# 11.net
KiCad netlist of a schematic drawn in Altium Designer
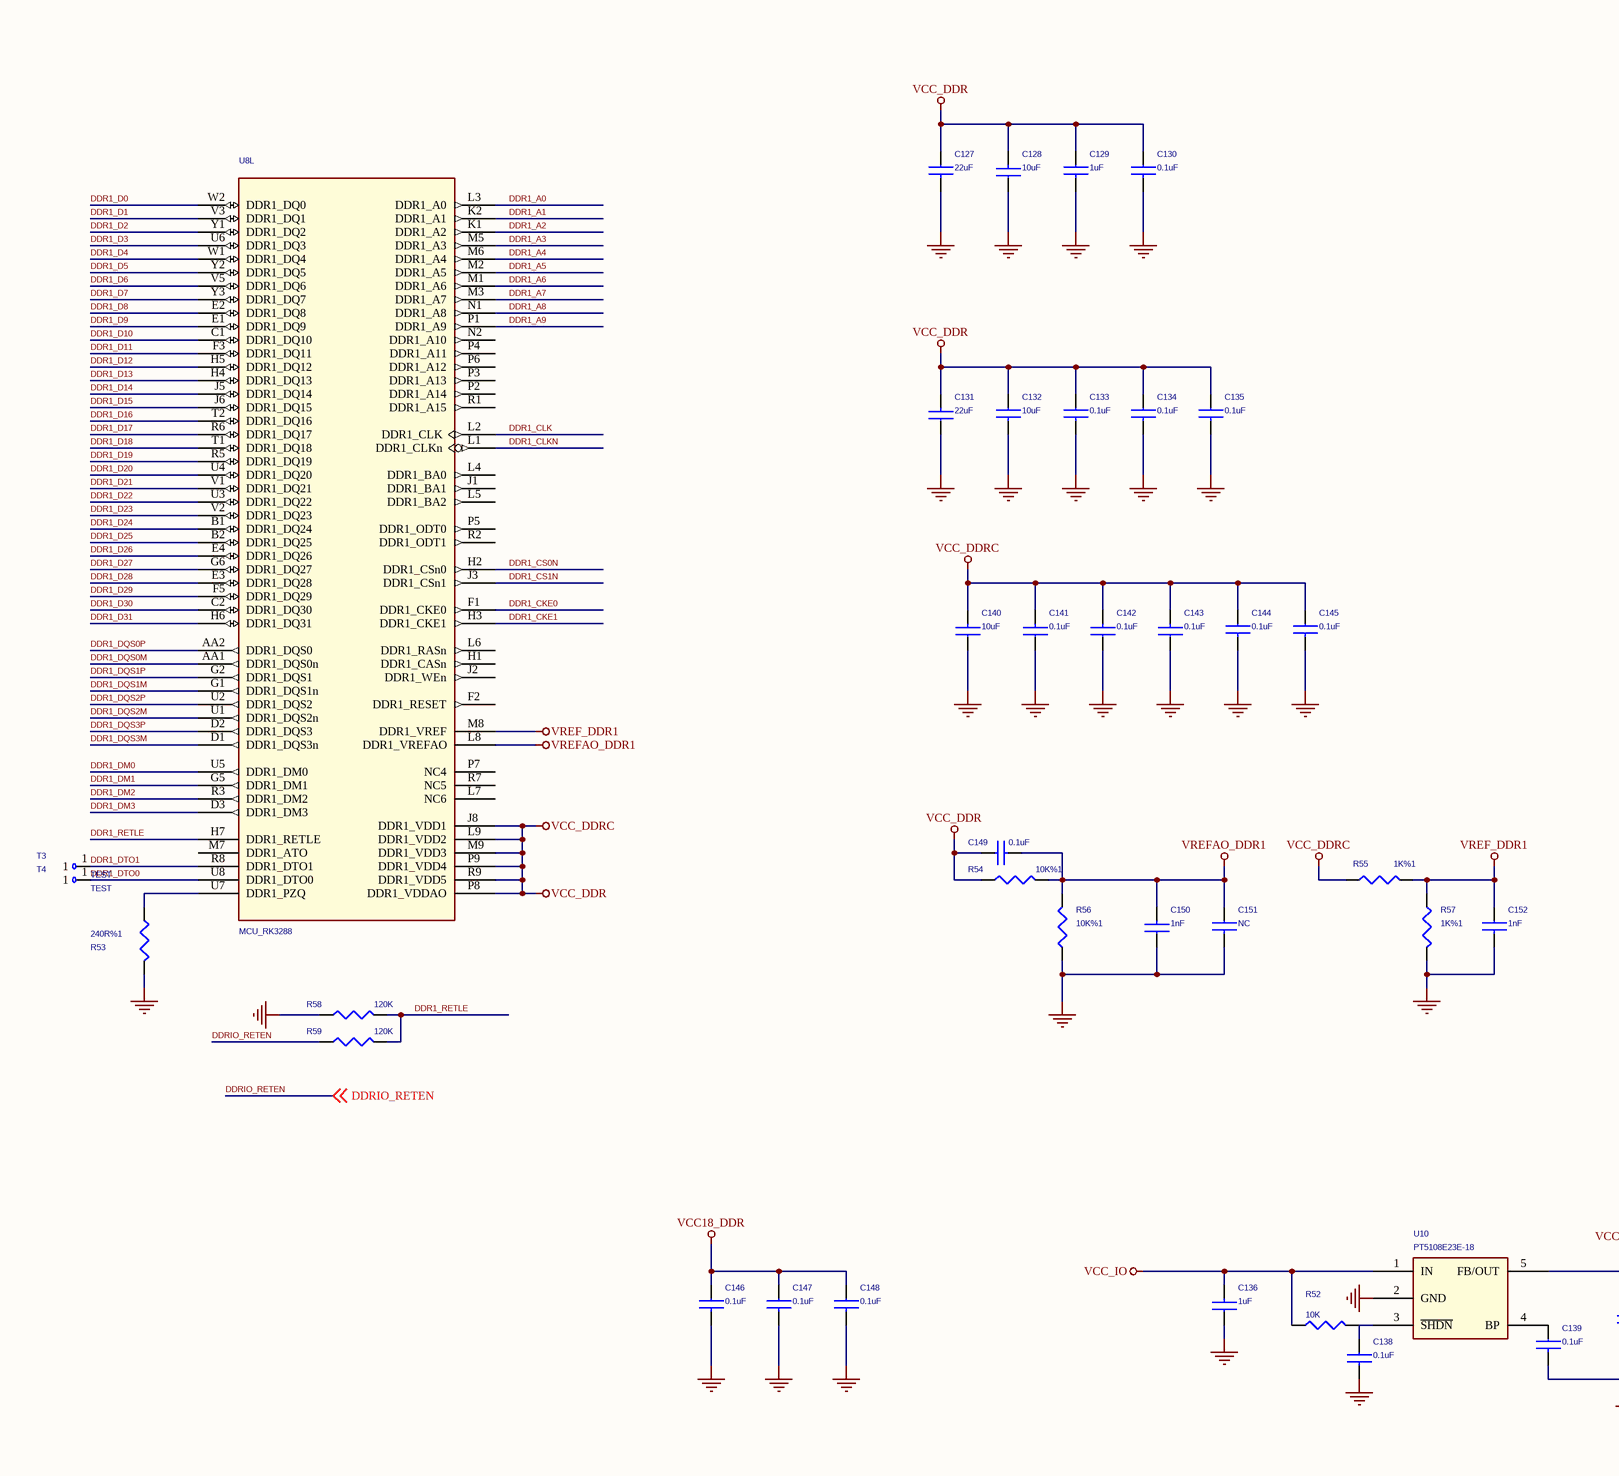
[diagram p0: 11.SchDoc, left]
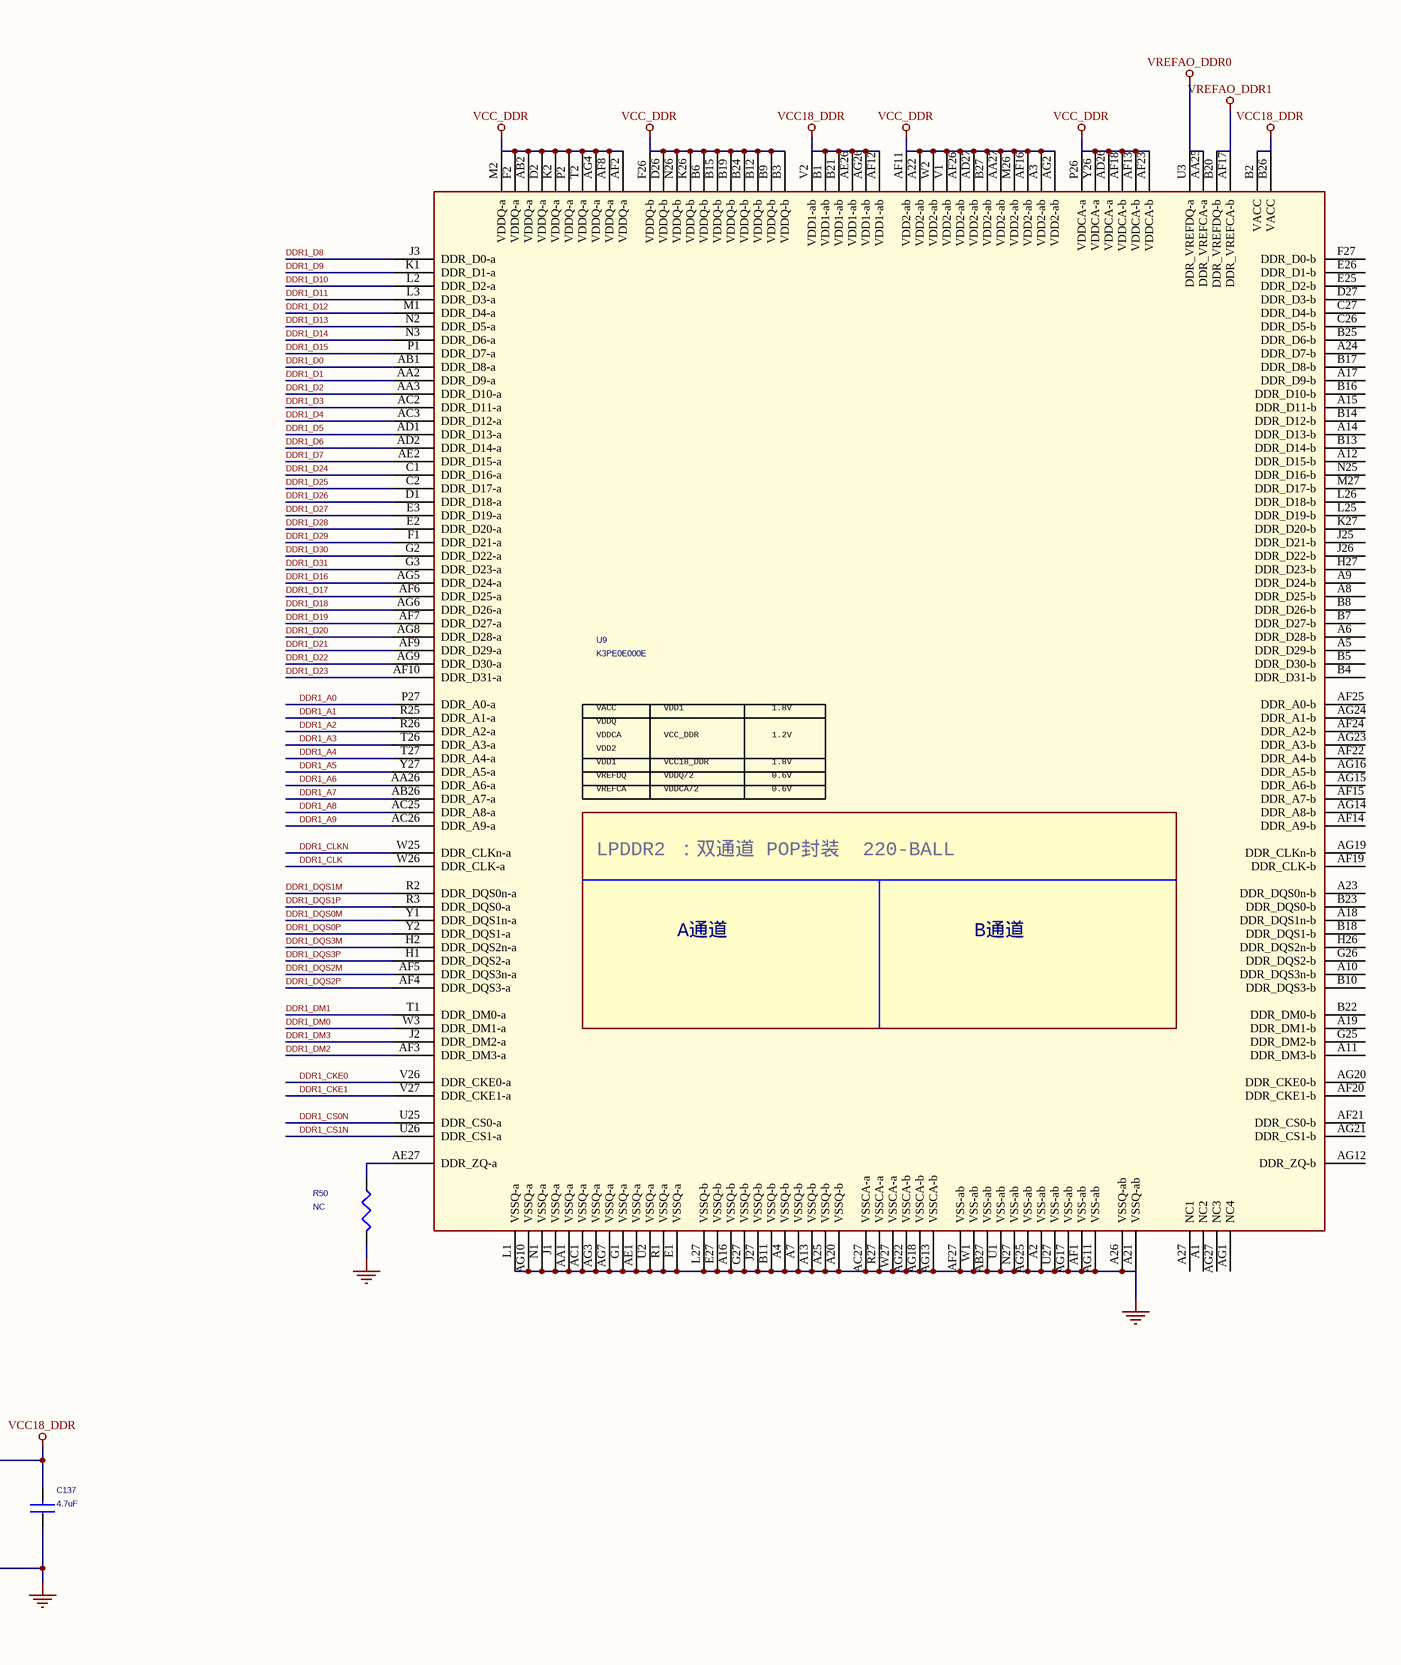
[diagram p1: 11.SchDoc, right]

(export (version "E")
  (design (tool "Eeschema 10.0.6"))
  (components
    (comp (ref "C127") (value "22uF") (footprint "C0805") (libsource (lib "*") (part "CAP NP_0_Dup1")))
    (comp (ref "C128") (value "10uF") (footprint "C0603") (libsource (lib "*") (part "CAP NP_4")))
    (comp (ref "C129") (value "1uF") (footprint "c0402") (libsource (lib "*") (part "CAP NP_0_Dup1")))
    (comp (ref "C130") (value "0.1uF") (footprint "c0402") (libsource (lib "*") (part "CAP NP_0_Dup1")))
    (comp (ref "C131") (value "22uF") (footprint "C0805") (libsource (lib "*") (part "CAP NP_4")))
    (comp (ref "C132") (value "10uF") (footprint "C0603") (libsource (lib "*") (part "CAP NP_0_Dup1")))
    (comp (ref "C133") (value "0.1uF") (footprint "c0402") (libsource (lib "*") (part "CAP NP_0_Dup1")))
    (comp (ref "C134") (value "0.1uF") (footprint "c0402") (libsource (lib "*") (part "CAP NP_0_Dup1")))
    (comp (ref "C135") (value "0.1uF") (footprint "C0201") (libsource (lib "*") (part "CAP NP_0_Dup1")))
    (comp (ref "C136")
      (value "1uF")
      (footprint "c0402")
      (description "CAP,MLCC,10uF,+/-10%,X5R,6.3V,SMD0805")
      (libsource (lib "*") (part "CAP NP_4"))
    )
    (comp (ref "C137")
      (value "4.7uF")
      (footprint "C0603")
      (description "CAP,MLCC,10uF,+/-10%,X5R,6.3V,SMD0805")
      (libsource (lib "*") (part "CAP NP_4"))
    )
    (comp (ref "C138")
      (value "0.1uF")
      (footprint "c0402")
      (description "CAP,MLCC,100nF,+/-10%,X7R,6.3V,SMD0402")
      (libsource (lib "*") (part "CAP NP_4"))
    )
    (comp (ref "C139")
      (value "0.1uF")
      (footprint "c0402")
      (description "CAP,MLCC,100nF,+/-10%,X7R,6.3V,SMD0402")
      (libsource (lib "*") (part "CAP NP_4"))
    )
    (comp (ref "C140") (value "10uF") (footprint "C0603") (libsource (lib "*") (part "CAP NP_4")))
    (comp (ref "C141") (value "0.1uF") (footprint "c0402") (libsource (lib "*") (part "CAP NP_4")))
    (comp (ref "C142") (value "0.1uF") (footprint "c0402") (libsource (lib "*") (part "CAP NP_4")))
    (comp (ref "C143") (value "0.1uF") (footprint "c0402") (libsource (lib "*") (part "CAP NP_4")))
    (comp (ref "C144") (value "0.1uF") (footprint "c0402") (libsource (lib "*") (part "CAP NP_0_Dup1")))
    (comp (ref "C145") (value "0.1uF") (footprint "c0402") (libsource (lib "*") (part "CAP NP_0_Dup1")))
    (comp (ref "C146") (value "0.1uF") (footprint "c0402") (libsource (lib "*") (part "CAP NP_0_Dup1")))
    (comp (ref "C147") (value "0.1uF") (footprint "c0402") (libsource (lib "*") (part "CAP NP_0_Dup1")))
    (comp (ref "C148") (value "0.1uF") (footprint "C0201") (libsource (lib "*") (part "CAP NP_0_Dup1")))
    (comp (ref "C149") (value "0.1uF") (footprint "c0402") (libsource (lib "*") (part "CAP NP_0_Dup1")))
    (comp (ref "C150") (value "1nF") (footprint "C0201") (libsource (lib "*") (part "CAP NP_0_Dup1")))
    (comp (ref "C151") (value "NC") (footprint "c0402") (libsource (lib "*") (part "CAP NP_0_Dup1")))
    (comp (ref "C152") (value "1nF") (footprint "c0402") (libsource (lib "*") (part "CAP NP_0_Dup1")))
    (comp (ref "R50")
      (value "NC")
      (footprint "r0402")
      (description "贴片电阻")
      (libsource (lib "*") (part "RESISTOR_0_Dup1"))
    )
    (comp (ref "R52")
      (value "10K")
      (footprint "r0402")
      (description "贴片电阻")
      (libsource (lib "*") (part "RESISTOR_0_Dup1"))
    )
    (comp (ref "R53")
      (value "240R%1")
      (footprint "r0402")
      (description "贴片电阻")
      (libsource (lib "*") (part "RESISTOR_0_Dup1"))
    )
    (comp (ref "R54")
      (value "10K%1")
      (footprint "r0402")
      (description "贴片电阻")
      (libsource (lib "*") (part "RESISTOR_0_Dup1"))
    )
    (comp (ref "R55")
      (value "1K%1")
      (footprint "r0402")
      (description "贴片电阻")
      (libsource (lib "*") (part "RESISTOR_0_Dup1"))
    )
    (comp (ref "R56")
      (value "10K%1")
      (footprint "r0402")
      (description "贴片电阻")
      (libsource (lib "*") (part "RESISTOR_0_Dup1"))
    )
    (comp (ref "R57")
      (value "1K%1")
      (footprint "r0402")
      (description "贴片电阻")
      (libsource (lib "*") (part "RESISTOR_0_Dup1"))
    )
    (comp (ref "R58")
      (value "120K")
      (footprint "r0402")
      (description "贴片电阻")
      (libsource (lib "*") (part "RESISTOR_0_Dup1"))
    )
    (comp (ref "R59")
      (value "120K")
      (footprint "r0402")
      (description "贴片电阻")
      (libsource (lib "*") (part "RESISTOR_0_Dup1"))
    )
    (comp (ref "T3") (value "TEST") (footprint "TEST") (libsource (lib "*") (part "TEST_0")))
    (comp (ref "T4") (value "TEST") (footprint "TEST") (libsource (lib "*") (part "TEST_0")))
    (comp (ref "U8")
      (value "MCU_RK3288")
      (footprint "BGA453-19X19")
      (libsource (lib "*") (part "MCU_RK3288_3"))
    )
    (comp (ref "U9")
      (value "K3PE0E000E")
      (footprint "FBGA220-14X14")
      (libsource (lib "*") (part "K3PE0E000E_1"))
    )
    (comp (ref "U10")
      (value "PT5108E23E-18")
      (footprint "SOT25")
      (description "LDO,PT5108E23E-33,VINmax=5.5V,Vout=3.3V,+/-2%,500mA,SOT-23-5")
      (libsource (lib "*") (part "DS8008_4"))
    )
  )
  (nets
    (net (code "1") (name "/DDR1_A0") (class "Default")
      (node (ref "U8") (pin "L3") (pinfunction "DDR1_A0_L3") (pintype "output"))
      (node (ref "U9") (pin "P27") (pinfunction "DDR_A0-a_P27") (pintype "passive"))
    )
    (net (code "2") (name "/DDR1_A1") (class "Default")
      (node (ref "U8") (pin "K2") (pinfunction "DDR1_A1_K2") (pintype "output"))
      (node (ref "U9") (pin "R25") (pinfunction "DDR_A1-a_R25") (pintype "passive"))
    )
    (net (code "3") (name "/DDR1_A2") (class "Default")
      (node (ref "U8") (pin "K1") (pinfunction "DDR1_A2_K1") (pintype "output"))
      (node (ref "U9") (pin "R26") (pinfunction "DDR_A2-a_R26") (pintype "passive"))
    )
    (net (code "4") (name "/DDR1_A3") (class "Default")
      (node (ref "U8") (pin "M5") (pinfunction "DDR1_A3_M5") (pintype "output"))
      (node (ref "U9") (pin "T26") (pinfunction "DDR_A3-a_T26") (pintype "passive"))
    )
    (net (code "5") (name "/DDR1_A4") (class "Default")
      (node (ref "U8") (pin "M6") (pinfunction "DDR1_A4_M6") (pintype "output"))
      (node (ref "U9") (pin "T27") (pinfunction "DDR_A4-a_T27") (pintype "passive"))
    )
    (net (code "6") (name "/DDR1_A5") (class "Default")
      (node (ref "U8") (pin "M2") (pinfunction "DDR1_A5_M2") (pintype "output"))
      (node (ref "U9") (pin "Y27") (pinfunction "DDR_A5-a_Y27") (pintype "passive"))
    )
    (net (code "7") (name "/DDR1_A6") (class "Default")
      (node (ref "U8") (pin "M1") (pinfunction "DDR1_A6_M1") (pintype "output"))
      (node (ref "U9") (pin "AA26") (pinfunction "DDR_A6-a_AA26") (pintype "passive"))
    )
    (net (code "8") (name "/DDR1_A7") (class "Default")
      (node (ref "U8") (pin "M3") (pinfunction "DDR1_A7_M3") (pintype "output"))
      (node (ref "U9") (pin "AB26") (pinfunction "DDR_A7-a_AB26") (pintype "passive"))
    )
    (net (code "9") (name "/DDR1_A8") (class "Default")
      (node (ref "U8") (pin "N1") (pinfunction "DDR1_A8_N1") (pintype "output"))
      (node (ref "U9") (pin "AC25") (pinfunction "DDR_A8-a_AC25") (pintype "passive"))
    )
    (net (code "10") (name "/DDR1_A9") (class "Default")
      (node (ref "U8") (pin "P1") (pinfunction "DDR1_A9_P1") (pintype "output"))
      (node (ref "U9") (pin "AC26") (pinfunction "DDR_A9-a_AC26") (pintype "passive"))
    )
    (net (code "11") (name "/DDR1_CKE0") (class "Default")
      (node (ref "U8") (pin "F1") (pinfunction "DDR1_CKE0_F1") (pintype "output"))
      (node (ref "U9") (pin "V26") (pinfunction "DDR_CKE0-a_V26") (pintype "passive"))
    )
    (net (code "12") (name "/DDR1_CKE1") (class "Default")
      (node (ref "U8") (pin "H3") (pinfunction "DDR1_CKE1_H3") (pintype "output"))
      (node (ref "U9") (pin "V27") (pinfunction "DDR_CKE1-a_V27") (pintype "passive"))
    )
    (net (code "13") (name "/DDR1_CLK") (class "Default")
      (node (ref "U8") (pin "L2") (pinfunction "DDR1_CLK_L2") (pintype "output"))
      (node (ref "U9") (pin "W26") (pinfunction "DDR_CLK-a_W26") (pintype "passive"))
    )
    (net (code "14") (name "/DDR1_CLKN") (class "Default")
      (node (ref "U8") (pin "L1") (pinfunction "DDR1_CLKn_L1") (pintype "output"))
      (node (ref "U9") (pin "W25") (pinfunction "DDR_CLKn-a_W25") (pintype "passive"))
    )
    (net (code "15") (name "/DDR1_CS0N") (class "Default")
      (node (ref "U8") (pin "H2") (pinfunction "DDR1_CSn0_H2") (pintype "output"))
      (node (ref "U9") (pin "U25") (pinfunction "DDR_CS0-a_U25") (pintype "passive"))
    )
    (net (code "16") (name "/DDR1_CS1N") (class "Default")
      (node (ref "U8") (pin "J3") (pinfunction "DDR1_CSn1_J3") (pintype "output"))
      (node (ref "U9") (pin "U26") (pinfunction "DDR_CS1-a_U26") (pintype "passive"))
    )
    (net (code "17") (name "/DDR1_D0") (class "Default")
      (node (ref "U8") (pin "W2") (pinfunction "DDR1_DQ0_W2") (pintype "bidirectional"))
      (node (ref "U9") (pin "AB1") (pinfunction "DDR_D8-a_AB1") (pintype "passive"))
    )
    (net (code "18") (name "/DDR1_D1") (class "Default")
      (node (ref "U8") (pin "V3") (pinfunction "DDR1_DQ1_V3") (pintype "bidirectional"))
      (node (ref "U9") (pin "AA2") (pinfunction "DDR_D9-a_AA2") (pintype "passive"))
    )
    (net (code "19") (name "/DDR1_D2") (class "Default")
      (node (ref "U8") (pin "Y1") (pinfunction "DDR1_DQ2_Y1") (pintype "bidirectional"))
      (node (ref "U9") (pin "AA3") (pinfunction "DDR_D10-a_AA3") (pintype "passive"))
    )
    (net (code "20") (name "/DDR1_D3") (class "Default")
      (node (ref "U8") (pin "U6") (pinfunction "DDR1_DQ3_U6") (pintype "bidirectional"))
      (node (ref "U9") (pin "AC2") (pinfunction "DDR_D11-a_AC2") (pintype "passive"))
    )
    (net (code "21") (name "/DDR1_D4") (class "Default")
      (node (ref "U8") (pin "W1") (pinfunction "DDR1_DQ4_W1") (pintype "bidirectional"))
      (node (ref "U9") (pin "AC3") (pinfunction "DDR_D12-a_AC3") (pintype "passive"))
    )
    (net (code "22") (name "/DDR1_D5") (class "Default")
      (node (ref "U8") (pin "Y2") (pinfunction "DDR1_DQ5_Y2") (pintype "bidirectional"))
      (node (ref "U9") (pin "AD1") (pinfunction "DDR_D13-a_AD1") (pintype "passive"))
    )
    (net (code "23") (name "/DDR1_D6") (class "Default")
      (node (ref "U8") (pin "V5") (pinfunction "DDR1_DQ6_V5") (pintype "bidirectional"))
      (node (ref "U9") (pin "AD2") (pinfunction "DDR_D14-a_AD2") (pintype "passive"))
    )
    (net (code "24") (name "/DDR1_D7") (class "Default")
      (node (ref "U8") (pin "Y3") (pinfunction "DDR1_DQ7_Y3") (pintype "bidirectional"))
      (node (ref "U9") (pin "AE2") (pinfunction "DDR_D15-a_AE2") (pintype "passive"))
    )
    (net (code "25") (name "/DDR1_D8") (class "Default")
      (node (ref "U8") (pin "E2") (pinfunction "DDR1_DQ8_E2") (pintype "bidirectional"))
      (node (ref "U9") (pin "J3") (pinfunction "DDR_D0-a_J3") (pintype "passive"))
    )
    (net (code "26") (name "/DDR1_D9") (class "Default")
      (node (ref "U8") (pin "E1") (pinfunction "DDR1_DQ9_E1") (pintype "bidirectional"))
      (node (ref "U9") (pin "K1") (pinfunction "DDR_D1-a_K1") (pintype "passive"))
    )
    (net (code "27") (name "/DDR1_D10") (class "Default")
      (node (ref "U8") (pin "C1") (pinfunction "DDR1_DQ10_C1") (pintype "bidirectional"))
      (node (ref "U9") (pin "L2") (pinfunction "DDR_D2-a_L2") (pintype "passive"))
    )
    (net (code "28") (name "/DDR1_D11") (class "Default")
      (node (ref "U8") (pin "F3") (pinfunction "DDR1_DQ11_F3") (pintype "bidirectional"))
      (node (ref "U9") (pin "L3") (pinfunction "DDR_D3-a_L3") (pintype "passive"))
    )
    (net (code "29") (name "/DDR1_D12") (class "Default")
      (node (ref "U8") (pin "H5") (pinfunction "DDR1_DQ12_H5") (pintype "bidirectional"))
      (node (ref "U9") (pin "M1") (pinfunction "DDR_D4-a_M1") (pintype "passive"))
    )
    (net (code "30") (name "/DDR1_D13") (class "Default")
      (node (ref "U8") (pin "H4") (pinfunction "DDR1_DQ13_H4") (pintype "bidirectional"))
      (node (ref "U9") (pin "N2") (pinfunction "DDR_D5-a_N2") (pintype "passive"))
    )
    (net (code "31") (name "/DDR1_D14") (class "Default")
      (node (ref "U8") (pin "J5") (pinfunction "DDR1_DQ14_J5") (pintype "bidirectional"))
      (node (ref "U9") (pin "N3") (pinfunction "DDR_D6-a_N3") (pintype "passive"))
    )
    (net (code "32") (name "/DDR1_D15") (class "Default")
      (node (ref "U8") (pin "J6") (pinfunction "DDR1_DQ15_J6") (pintype "bidirectional"))
      (node (ref "U9") (pin "P1") (pinfunction "DDR_D7-a_P1") (pintype "passive"))
    )
    (net (code "33") (name "/DDR1_D16") (class "Default")
      (node (ref "U8") (pin "T2") (pinfunction "DDR1_DQ16_T2") (pintype "bidirectional"))
      (node (ref "U9") (pin "AG5") (pinfunction "DDR_D24-a_AG5") (pintype "passive"))
    )
    (net (code "34") (name "/DDR1_D17") (class "Default")
      (node (ref "U8") (pin "R6") (pinfunction "DDR1_DQ17_R6") (pintype "bidirectional"))
      (node (ref "U9") (pin "AF6") (pinfunction "DDR_D25-a_AF6") (pintype "passive"))
    )
    (net (code "35") (name "/DDR1_D18") (class "Default")
      (node (ref "U8") (pin "T1") (pinfunction "DDR1_DQ18_T1") (pintype "bidirectional"))
      (node (ref "U9") (pin "AG6") (pinfunction "DDR_D26-a_AG6") (pintype "passive"))
    )
    (net (code "36") (name "/DDR1_D19") (class "Default")
      (node (ref "U8") (pin "R5") (pinfunction "DDR1_DQ19_R5") (pintype "bidirectional"))
      (node (ref "U9") (pin "AF7") (pinfunction "DDR_D27-a_AF7") (pintype "passive"))
    )
    (net (code "37") (name "/DDR1_D20") (class "Default")
      (node (ref "U8") (pin "U4") (pinfunction "DDR1_DQ20_U4") (pintype "bidirectional"))
      (node (ref "U9") (pin "AG8") (pinfunction "DDR_D28-a_AG8") (pintype "passive"))
    )
    (net (code "38") (name "/DDR1_D21") (class "Default")
      (node (ref "U8") (pin "V1") (pinfunction "DDR1_DQ21_V1") (pintype "bidirectional"))
      (node (ref "U9") (pin "AF9") (pinfunction "DDR_D29-a_AF9") (pintype "passive"))
    )
    (net (code "39") (name "/DDR1_D22") (class "Default")
      (node (ref "U8") (pin "U3") (pinfunction "DDR1_DQ22_U3") (pintype "bidirectional"))
      (node (ref "U9") (pin "AG9") (pinfunction "DDR_D30-a_AG9") (pintype "passive"))
    )
    (net (code "40") (name "/DDR1_D23") (class "Default")
      (node (ref "U8") (pin "V2") (pinfunction "DDR1_DQ23_V2") (pintype "bidirectional"))
      (node (ref "U9") (pin "AF10") (pinfunction "DDR_D31-a_AF10") (pintype "passive"))
    )
    (net (code "41") (name "/DDR1_D24") (class "Default")
      (node (ref "U8") (pin "B1") (pinfunction "DDR1_DQ24_B1") (pintype "bidirectional"))
      (node (ref "U9") (pin "C1") (pinfunction "DDR_D16-a_C1") (pintype "passive"))
    )
    (net (code "42") (name "/DDR1_D25") (class "Default")
      (node (ref "U8") (pin "B2") (pinfunction "DDR1_DQ25_B2") (pintype "bidirectional"))
      (node (ref "U9") (pin "C2") (pinfunction "DDR_D17-a_C2") (pintype "passive"))
    )
    (net (code "43") (name "/DDR1_D26") (class "Default")
      (node (ref "U8") (pin "E4") (pinfunction "DDR1_DQ26_E4") (pintype "bidirectional"))
      (node (ref "U9") (pin "D1") (pinfunction "DDR_D18-a_D1") (pintype "passive"))
    )
    (net (code "44") (name "/DDR1_D27") (class "Default")
      (node (ref "U8") (pin "G6") (pinfunction "DDR1_DQ27_G6") (pintype "bidirectional"))
      (node (ref "U9") (pin "E3") (pinfunction "DDR_D19-a_E3") (pintype "passive"))
    )
    (net (code "45") (name "/DDR1_D28") (class "Default")
      (node (ref "U8") (pin "E3") (pinfunction "DDR1_DQ28_E3") (pintype "bidirectional"))
      (node (ref "U9") (pin "E2") (pinfunction "DDR_D20-a_E2") (pintype "passive"))
    )
    (net (code "46") (name "/DDR1_D29") (class "Default")
      (node (ref "U8") (pin "F5") (pinfunction "DDR1_DQ29_F5") (pintype "bidirectional"))
      (node (ref "U9") (pin "F1") (pinfunction "DDR_D21-a_F1") (pintype "passive"))
    )
    (net (code "47") (name "/DDR1_D30") (class "Default")
      (node (ref "U8") (pin "C2") (pinfunction "DDR1_DQ30_C2") (pintype "bidirectional"))
      (node (ref "U9") (pin "G2") (pinfunction "DDR_D22-a_G2") (pintype "passive"))
    )
    (net (code "48") (name "/DDR1_D31") (class "Default")
      (node (ref "U8") (pin "H6") (pinfunction "DDR1_DQ31_H6") (pintype "bidirectional"))
      (node (ref "U9") (pin "G3") (pinfunction "DDR_D23-a_G3") (pintype "passive"))
    )
    (net (code "49") (name "/DDR1_DM0") (class "Default")
      (node (ref "U8") (pin "U5") (pinfunction "DDR1_DM0_U5") (pintype "output"))
      (node (ref "U9") (pin "W3") (pinfunction "DDR_DM1-a_W3") (pintype "passive"))
    )
    (net (code "50") (name "/DDR1_DM1") (class "Default")
      (node (ref "U8") (pin "G5") (pinfunction "DDR1_DM1_G5") (pintype "output"))
      (node (ref "U9") (pin "T1") (pinfunction "DDR_DM0-a_T1") (pintype "passive"))
    )
    (net (code "51") (name "/DDR1_DM2") (class "Default")
      (node (ref "U8") (pin "R3") (pinfunction "DDR1_DM2_R3") (pintype "output"))
      (node (ref "U9") (pin "AF3") (pinfunction "DDR_DM3-a_AF3") (pintype "passive"))
    )
    (net (code "52") (name "/DDR1_DM3") (class "Default")
      (node (ref "U8") (pin "D3") (pinfunction "DDR1_DM3_D3") (pintype "output"))
      (node (ref "U9") (pin "J2") (pinfunction "DDR_DM2-a_J2") (pintype "passive"))
    )
    (net (code "53") (name "/DDR1_DQS0M") (class "Default")
      (node (ref "U8") (pin "AA1") (pinfunction "DDR1_DQS0n_AA1") (pintype "output"))
      (node (ref "U9") (pin "Y1") (pinfunction "DDR_DQS1n-a_Y1") (pintype "passive"))
    )
    (net (code "54") (name "/DDR1_DQS0P") (class "Default")
      (node (ref "U8") (pin "AA2") (pinfunction "DDR1_DQS0_AA2") (pintype "output"))
      (node (ref "U9") (pin "Y2") (pinfunction "DDR_DQS1-a_Y2") (pintype "passive"))
    )
    (net (code "55") (name "/DDR1_DQS1M") (class "Default")
      (node (ref "U8") (pin "G1") (pinfunction "DDR1_DQS1n_G1") (pintype "output"))
      (node (ref "U9") (pin "R2") (pinfunction "DDR_DQS0n-a_R2") (pintype "passive"))
    )
    (net (code "56") (name "/DDR1_DQS1P") (class "Default")
      (node (ref "U8") (pin "G2") (pinfunction "DDR1_DQS1_G2") (pintype "output"))
      (node (ref "U9") (pin "R3") (pinfunction "DDR_DQS0-a_R3") (pintype "passive"))
    )
    (net (code "57") (name "/DDR1_DQS2M") (class "Default")
      (node (ref "U8") (pin "U1") (pinfunction "DDR1_DQS2n_U1") (pintype "output"))
      (node (ref "U9") (pin "AF5") (pinfunction "DDR_DQS3n-a_AF5") (pintype "passive"))
    )
    (net (code "58") (name "/DDR1_DQS2P") (class "Default")
      (node (ref "U8") (pin "U2") (pinfunction "DDR1_DQS2_U2") (pintype "output"))
      (node (ref "U9") (pin "AF4") (pinfunction "DDR_DQS3-a_AF4") (pintype "passive"))
    )
    (net (code "59") (name "/DDR1_DQS3M") (class "Default")
      (node (ref "U8") (pin "D1") (pinfunction "DDR1_DQS3n_D1") (pintype "output"))
      (node (ref "U9") (pin "H2") (pinfunction "DDR_DQS2n-a_H2") (pintype "passive"))
    )
    (net (code "60") (name "/DDR1_DQS3P") (class "Default")
      (node (ref "U8") (pin "D2") (pinfunction "DDR1_DQS3_D2") (pintype "output"))
      (node (ref "U9") (pin "H1") (pinfunction "DDR_DQS2-a_H1") (pintype "passive"))
    )
    (net (code "61") (name "/DDR1_DTO0") (class "Default")
      (node (ref "T4") (pin "1") (pinfunction "1_1") (pintype "passive"))
      (node (ref "U8") (pin "U8") (pinfunction "DDR1_DTO0_U8") (pintype "passive"))
    )
    (net (code "62") (name "/DDR1_DTO1") (class "Default")
      (node (ref "T3") (pin "1") (pinfunction "1_1") (pintype "passive"))
      (node (ref "U8") (pin "R8") (pinfunction "DDR1_DTO1_R8") (pintype "passive"))
    )
    (net (code "63") (name "/DDR1_RETLE") (class "Default")
      (node (ref "R58") (pin "1") (pinfunction "1_1") (pintype "passive"))
      (node (ref "R59") (pin "1") (pinfunction "1_1") (pintype "passive"))
      (node (ref "U8") (pin "H7") (pinfunction "DDR1_RETLE_H7") (pintype "passive"))
    )
    (net (code "64") (name "DDRIO_RETEN") (class "Default")
      (node (ref "R59") (pin "2") (pinfunction "2_2") (pintype "passive"))
    )
    (net (code "65") (name "GND") (class "Default")
      (node (ref "C127") (pin "2") (pinfunction "2_2") (pintype "passive"))
      (node (ref "C128") (pin "1") (pinfunction "1_1") (pintype "passive"))
      (node (ref "C129") (pin "2") (pinfunction "2_2") (pintype "passive"))
      (node (ref "C130") (pin "2") (pinfunction "2_2") (pintype "passive"))
      (node (ref "C131") (pin "1") (pinfunction "1_1") (pintype "passive"))
      (node (ref "C132") (pin "2") (pinfunction "2_2") (pintype "passive"))
      (node (ref "C133") (pin "2") (pinfunction "2_2") (pintype "passive"))
      (node (ref "C134") (pin "2") (pinfunction "2_2") (pintype "passive"))
      (node (ref "C135") (pin "2") (pinfunction "2_2") (pintype "passive"))
      (node (ref "C136") (pin "1") (pinfunction "1_1") (pintype "passive"))
      (node (ref "C137") (pin "1") (pinfunction "1_1") (pintype "passive"))
      (node (ref "C138") (pin "2") (pinfunction "2_2") (pintype "passive"))
      (node (ref "C139") (pin "2") (pinfunction "2_2") (pintype "passive"))
      (node (ref "C140") (pin "1") (pinfunction "1_1") (pintype "passive"))
      (node (ref "C141") (pin "1") (pinfunction "1_1") (pintype "passive"))
      (node (ref "C142") (pin "1") (pinfunction "1_1") (pintype "passive"))
      (node (ref "C143") (pin "1") (pinfunction "1_1") (pintype "passive"))
      (node (ref "C144") (pin "2") (pinfunction "2_2") (pintype "passive"))
      (node (ref "C145") (pin "2") (pinfunction "2_2") (pintype "passive"))
      (node (ref "C146") (pin "2") (pinfunction "2_2") (pintype "passive"))
      (node (ref "C147") (pin "2") (pinfunction "2_2") (pintype "passive"))
      (node (ref "C148") (pin "2") (pinfunction "2_2") (pintype "passive"))
      (node (ref "C150") (pin "1") (pinfunction "1_1") (pintype "passive"))
      (node (ref "C151") (pin "2") (pinfunction "2_2") (pintype "passive"))
      (node (ref "C152") (pin "2") (pinfunction "2_2") (pintype "passive"))
      (node (ref "R50") (pin "2") (pinfunction "2_2") (pintype "passive"))
      (node (ref "R53") (pin "2") (pinfunction "2_2") (pintype "passive"))
      (node (ref "R56") (pin "1") (pinfunction "1_1") (pintype "passive"))
      (node (ref "R57") (pin "2") (pinfunction "2_2") (pintype "passive"))
      (node (ref "R58") (pin "2") (pinfunction "2_2") (pintype "passive"))
      (node (ref "U10") (pin "2") (pinfunction "GND_2") (pintype "passive"))
      (node (ref "U9") (pin "A13") (pinfunction "VSSQ-b_A13") (pintype "power_in"))
      (node (ref "U9") (pin "A16") (pinfunction "VSSQ-b_A16") (pintype "power_in"))
      (node (ref "U9") (pin "A2") (pinfunction "VSS-ab_A2") (pintype "power_in"))
      (node (ref "U9") (pin "A20") (pinfunction "VSSQ-b_A20") (pintype "power_in"))
      (node (ref "U9") (pin "A21") (pinfunction "VSSQ-ab_A21") (pintype "power_in"))
      (node (ref "U9") (pin "A25") (pinfunction "VSSQ-b_A25") (pintype "power_in"))
      (node (ref "U9") (pin "A26") (pinfunction "VSSQ-ab_A26") (pintype "power_in"))
      (node (ref "U9") (pin "A4") (pinfunction "VSSQ-b_A4") (pintype "power_in"))
      (node (ref "U9") (pin "A7") (pinfunction "VSSQ-b_A7") (pintype "power_in"))
      (node (ref "U9") (pin "AA1") (pinfunction "VSSQ-a_AA1") (pintype "power_in"))
      (node (ref "U9") (pin "AB27") (pinfunction "VSS-ab_AB27") (pintype "power_in"))
      (node (ref "U9") (pin "AC1") (pinfunction "VSSQ-a_AC1") (pintype "power_in"))
      (node (ref "U9") (pin "AC27") (pinfunction "VSSCA-a_AC27") (pintype "power_in"))
      (node (ref "U9") (pin "AE1") (pinfunction "VSSQ-a_AE1") (pintype "power_in"))
      (node (ref "U9") (pin "AF1") (pinfunction "VSS-ab_AF1") (pintype "power_in"))
      (node (ref "U9") (pin "AF27") (pinfunction "VSS-ab_AF27") (pintype "power_in"))
      (node (ref "U9") (pin "AG10") (pinfunction "VSSQ-a_AG10") (pintype "power_in"))
      (node (ref "U9") (pin "AG11") (pinfunction "VSS-ab_AG11") (pintype "power_in"))
      (node (ref "U9") (pin "AG13") (pinfunction "VSSCA-b_AG13") (pintype "power_in"))
      (node (ref "U9") (pin "AG17") (pinfunction "VSS-ab_AG17") (pintype "power_in"))
      (node (ref "U9") (pin "AG18") (pinfunction "VSSCA-b_AG18") (pintype "power_in"))
      (node (ref "U9") (pin "AG22") (pinfunction "VSSCA-b_AG22") (pintype "power_in"))
      (node (ref "U9") (pin "AG25") (pinfunction "VSS-ab_AG25") (pintype "power_in"))
      (node (ref "U9") (pin "AG3") (pinfunction "VSSQ-a_AG3") (pintype "power_in"))
      (node (ref "U9") (pin "AG7") (pinfunction "VSSQ-a_AG7") (pintype "power_in"))
      (node (ref "U9") (pin "B11") (pinfunction "VSSQ-b_B11") (pintype "power_in"))
      (node (ref "U9") (pin "E1") (pinfunction "VSSQ-a_E1") (pintype "power_in"))
      (node (ref "U9") (pin "E27") (pinfunction "VSSQ-b_E27") (pintype "power_in"))
      (node (ref "U9") (pin "G1") (pinfunction "VSSQ-a_G1") (pintype "power_in"))
      (node (ref "U9") (pin "G27") (pinfunction "VSSQ-b_G27") (pintype "power_in"))
      (node (ref "U9") (pin "J1") (pinfunction "VSSQ-a_J1") (pintype "power_in"))
      (node (ref "U9") (pin "J27") (pinfunction "VSSQ-b_J27") (pintype "power_in"))
      (node (ref "U9") (pin "L1") (pinfunction "VSSQ-a_L1") (pintype "power_in"))
      (node (ref "U9") (pin "L27") (pinfunction "VSSQ-b_L27") (pintype "power_in"))
      (node (ref "U9") (pin "N1") (pinfunction "VSSQ-a_N1") (pintype "power_in"))
      (node (ref "U9") (pin "N27") (pinfunction "VSS-ab_N27") (pintype "power_in"))
      (node (ref "U9") (pin "R1") (pinfunction "VSSQ-a_R1") (pintype "power_in"))
      (node (ref "U9") (pin "R27") (pinfunction "VSSCA-a_R27") (pintype "power_in"))
      (node (ref "U9") (pin "U1") (pinfunction "VSS-ab_U1") (pintype "power_in"))
      (node (ref "U9") (pin "U2") (pinfunction "VSSQ-a_U2") (pintype "power_in"))
      (node (ref "U9") (pin "U27") (pinfunction "VSS-ab_U27") (pintype "power_in"))
      (node (ref "U9") (pin "W1") (pinfunction "VSS-ab_W1") (pintype "power_in"))
      (node (ref "U9") (pin "W27") (pinfunction "VSSCA-a_W27") (pintype "power_in"))
    )
    (net (code "66") (name "Net-(U8L-DDR1_PZQ)") (class "Default")
      (node (ref "R53") (pin "1") (pinfunction "1_1") (pintype "passive"))
      (node (ref "U8") (pin "U7") (pinfunction "DDR1_PZQ_U7") (pintype "passive"))
    )
    (net (code "67") (name "Net-(U9-DDR_ZQ-a)") (class "Default")
      (node (ref "R50") (pin "1") (pinfunction "1_1") (pintype "passive"))
      (node (ref "U9") (pin "AE27") (pinfunction "DDR_ZQ-a_AE27") (pintype "passive"))
    )
    (net (code "68") (name "Net-(U10-BP)") (class "Default")
      (node (ref "C139") (pin "1") (pinfunction "1_1") (pintype "passive"))
      (node (ref "U10") (pin "4") (pinfunction "BP_4") (pintype "passive"))
    )
    (net (code "69") (name "Net-(U10-~{SHDN})") (class "Default")
      (node (ref "C138") (pin "1") (pinfunction "1_1") (pintype "passive"))
      (node (ref "R52") (pin "2") (pinfunction "2_2") (pintype "passive"))
      (node (ref "U10") (pin "3") (pinfunction "~{SHDN}_3") (pintype "passive"))
    )
    (net (code "70") (name "VCC18_DDR") (class "Default")
      (node (ref "C137") (pin "2") (pinfunction "2_2") (pintype "passive"))
      (node (ref "C146") (pin "1") (pinfunction "1_1") (pintype "passive"))
      (node (ref "C147") (pin "1") (pinfunction "1_1") (pintype "passive"))
      (node (ref "C148") (pin "1") (pinfunction "1_1") (pintype "passive"))
      (node (ref "U10") (pin "5") (pinfunction "FB/OUT_5") (pintype "passive"))
      (node (ref "U9") (pin "AE26") (pinfunction "VDD1-ab_AE26") (pintype "power_in"))
      (node (ref "U9") (pin "AF12") (pinfunction "VDD1-ab_AF12") (pintype "power_in"))
      (node (ref "U9") (pin "AG26") (pinfunction "VDD1-ab_AG26") (pintype "power_in"))
      (node (ref "U9") (pin "B1") (pinfunction "VDD1-ab_B1") (pintype "power_in"))
      (node (ref "U9") (pin "B2") (pinfunction "VACC_B2") (pintype "power_in"))
      (node (ref "U9") (pin "B21") (pinfunction "VDD1-ab_B21") (pintype "power_in"))
      (node (ref "U9") (pin "B26") (pinfunction "VACC_B26") (pintype "power_in"))
      (node (ref "U9") (pin "V2") (pinfunction "VDD1-ab_V2") (pintype "power_in"))
    )
    (net (code "71") (name "VCC_DDR") (class "Default")
      (node (ref "C127") (pin "1") (pinfunction "1_1") (pintype "passive"))
      (node (ref "C128") (pin "2") (pinfunction "2_2") (pintype "passive"))
      (node (ref "C129") (pin "1") (pinfunction "1_1") (pintype "passive"))
      (node (ref "C130") (pin "1") (pinfunction "1_1") (pintype "passive"))
      (node (ref "C131") (pin "2") (pinfunction "2_2") (pintype "passive"))
      (node (ref "C132") (pin "1") (pinfunction "1_1") (pintype "passive"))
      (node (ref "C133") (pin "1") (pinfunction "1_1") (pintype "passive"))
      (node (ref "C134") (pin "1") (pinfunction "1_1") (pintype "passive"))
      (node (ref "C135") (pin "1") (pinfunction "1_1") (pintype "passive"))
      (node (ref "C140") (pin "2") (pinfunction "2_2") (pintype "passive"))
      (node (ref "C141") (pin "2") (pinfunction "2_2") (pintype "passive"))
      (node (ref "C142") (pin "2") (pinfunction "2_2") (pintype "passive"))
      (node (ref "C143") (pin "2") (pinfunction "2_2") (pintype "passive"))
      (node (ref "C144") (pin "1") (pinfunction "1_1") (pintype "passive"))
      (node (ref "C145") (pin "1") (pinfunction "1_1") (pintype "passive"))
      (node (ref "C149") (pin "1") (pinfunction "1_1") (pintype "passive"))
      (node (ref "R54") (pin "1") (pinfunction "1_1") (pintype "passive"))
      (node (ref "R55") (pin "1") (pinfunction "1_1") (pintype "passive"))
      (node (ref "U8") (pin "J8") (pinfunction "DDR1_VDD1_J8") (pintype "power_in"))
      (node (ref "U8") (pin "L9") (pinfunction "DDR1_VDD2_L9") (pintype "power_in"))
      (node (ref "U8") (pin "M9") (pinfunction "DDR1_VDD3_M9") (pintype "power_in"))
      (node (ref "U8") (pin "P8") (pinfunction "DDR1_VDDAO_P8") (pintype "power_in"))
      (node (ref "U8") (pin "P9") (pinfunction "DDR1_VDD4_P9") (pintype "power_in"))
      (node (ref "U8") (pin "R9") (pinfunction "DDR1_VDD5_R9") (pintype "power_in"))
      (node (ref "U9") (pin "A22") (pinfunction "VDD2-ab_A22") (pintype "power_in"))
      (node (ref "U9") (pin "A3") (pinfunction "VDD2-ab_A3") (pintype "power_in"))
      (node (ref "U9") (pin "AA27") (pinfunction "VDD2-ab_AA27") (pintype "power_in"))
      (node (ref "U9") (pin "AB2") (pinfunction "VDDQ-a_AB2") (pintype "power_in"))
      (node (ref "U9") (pin "AD26") (pinfunction "VDDCA-a_AD26") (pintype "power_in"))
      (node (ref "U9") (pin "AD27") (pinfunction "VDD2-ab_AD27") (pintype "power_in"))
      (node (ref "U9") (pin "AF11") (pinfunction "VDD2-ab_AF11") (pintype "power_in"))
      (node (ref "U9") (pin "AF13") (pinfunction "VDDCA-b_AF13") (pintype "power_in"))
      (node (ref "U9") (pin "AF16") (pinfunction "VDD2-ab_AF16") (pintype "power_in"))
      (node (ref "U9") (pin "AF18") (pinfunction "VDDCA-b_AF18") (pintype "power_in"))
      (node (ref "U9") (pin "AF2") (pinfunction "VDDQ-a_AF2") (pintype "power_in"))
      (node (ref "U9") (pin "AF23") (pinfunction "VDDCA-b_AF23") (pintype "power_in"))
      (node (ref "U9") (pin "AF26") (pinfunction "VDD2-ab_AF26") (pintype "power_in"))
      (node (ref "U9") (pin "AF8") (pinfunction "VDDQ-a_AF8") (pintype "power_in"))
      (node (ref "U9") (pin "AG2") (pinfunction "VDD2-ab_AG2") (pintype "power_in"))
      (node (ref "U9") (pin "AG4") (pinfunction "VDDQ-a_AG4") (pintype "power_in"))
      (node (ref "U9") (pin "B12") (pinfunction "VDDQ-b_B12") (pintype "power_in"))
      (node (ref "U9") (pin "B15") (pinfunction "VDDQ-b_B15") (pintype "power_in"))
      (node (ref "U9") (pin "B19") (pinfunction "VDDQ-b_B19") (pintype "power_in"))
      (node (ref "U9") (pin "B24") (pinfunction "VDDQ-b_B24") (pintype "power_in"))
      (node (ref "U9") (pin "B27") (pinfunction "VDD2-ab_B27") (pintype "power_in"))
      (node (ref "U9") (pin "B3") (pinfunction "VDDQ-b_B3") (pintype "power_in"))
      (node (ref "U9") (pin "B6") (pinfunction "VDDQ-b_B6") (pintype "power_in"))
      (node (ref "U9") (pin "B9") (pinfunction "VDDQ-b_B9") (pintype "power_in"))
      (node (ref "U9") (pin "D2") (pinfunction "VDDQ-a_D2") (pintype "power_in"))
      (node (ref "U9") (pin "D26") (pinfunction "VDDQ-b_D26") (pintype "power_in"))
      (node (ref "U9") (pin "F2") (pinfunction "VDDQ-a_F2") (pintype "power_in"))
      (node (ref "U9") (pin "F26") (pinfunction "VDDQ-b_F26") (pintype "power_in"))
      (node (ref "U9") (pin "K2") (pinfunction "VDDQ-a_K2") (pintype "power_in"))
      (node (ref "U9") (pin "K26") (pinfunction "VDDQ-b_K26") (pintype "power_in"))
      (node (ref "U9") (pin "M2") (pinfunction "VDDQ-a_M2") (pintype "power_in"))
      (node (ref "U9") (pin "M26") (pinfunction "VDD2-ab_M26") (pintype "power_in"))
      (node (ref "U9") (pin "N26") (pinfunction "VDDQ-b_N26") (pintype "power_in"))
      (node (ref "U9") (pin "P2") (pinfunction "VDDQ-a_P2") (pintype "power_in"))
      (node (ref "U9") (pin "P26") (pinfunction "VDDCA-a_P26") (pintype "power_in"))
      (node (ref "U9") (pin "T2") (pinfunction "VDDQ-a_T2") (pintype "power_in"))
      (node (ref "U9") (pin "V1") (pinfunction "VDD2-ab_V1") (pintype "power_in"))
      (node (ref "U9") (pin "W2") (pinfunction "VDD2-ab_W2") (pintype "power_in"))
      (node (ref "U9") (pin "Y26") (pinfunction "VDDCA-a_Y26") (pintype "power_in"))
    )
    (net (code "72") (name "VCC_IO") (class "Default")
      (node (ref "C136") (pin "2") (pinfunction "2_2") (pintype "passive"))
      (node (ref "R52") (pin "1") (pinfunction "1_1") (pintype "passive"))
      (node (ref "U10") (pin "1") (pinfunction "IN_1") (pintype "passive"))
    )
    (net (code "73") (name "VREFAO_DDR0") (class "Default")
      (node (ref "U9") (pin "AA25") (pinfunction "DDR_VREFCA-a_AA25") (pintype "power_in"))
      (node (ref "U9") (pin "U3") (pinfunction "DDR_VREFDQ-a_U3") (pintype "power_in"))
    )
    (net (code "74") (name "VREFAO_DDR1") (class "Default")
      (node (ref "C149") (pin "2") (pinfunction "2_2") (pintype "passive"))
      (node (ref "C150") (pin "2") (pinfunction "2_2") (pintype "passive"))
      (node (ref "C151") (pin "1") (pinfunction "1_1") (pintype "passive"))
      (node (ref "R54") (pin "2") (pinfunction "2_2") (pintype "passive"))
      (node (ref "R56") (pin "2") (pinfunction "2_2") (pintype "passive"))
      (node (ref "U8") (pin "L8") (pinfunction "DDR1_VREFAO_L8") (pintype "power_in"))
      (node (ref "U9") (pin "AF17") (pinfunction "DDR_VREFCA-b_AF17") (pintype "power_in"))
      (node (ref "U9") (pin "B20") (pinfunction "DDR_VREFDQ-b_B20") (pintype "power_in"))
    )
    (net (code "75") (name "VREF_DDR1") (class "Default")
      (node (ref "C152") (pin "1") (pinfunction "1_1") (pintype "passive"))
      (node (ref "R55") (pin "2") (pinfunction "2_2") (pintype "passive"))
      (node (ref "R57") (pin "1") (pinfunction "1_1") (pintype "passive"))
      (node (ref "U8") (pin "M8") (pinfunction "DDR1_VREF_M8") (pintype "power_in"))
    )
    (net (code "76") (name "unconnected-(U8L-DDR1_A10-PadN2)") (class "Default")
      (node (ref "U8") (pin "N2") (pinfunction "DDR1_A10_N2") (pintype "output"))
    )
    (net (code "77") (name "unconnected-(U8L-DDR1_A11-PadP4)") (class "Default")
      (node (ref "U8") (pin "P4") (pinfunction "DDR1_A11_P4") (pintype "output"))
    )
    (net (code "78") (name "unconnected-(U8L-DDR1_A12-PadP6)") (class "Default")
      (node (ref "U8") (pin "P6") (pinfunction "DDR1_A12_P6") (pintype "output"))
    )
    (net (code "79") (name "unconnected-(U8L-DDR1_A13-PadP3)") (class "Default")
      (node (ref "U8") (pin "P3") (pinfunction "DDR1_A13_P3") (pintype "output"))
    )
    (net (code "80") (name "unconnected-(U8L-DDR1_A14-PadP2)") (class "Default")
      (node (ref "U8") (pin "P2") (pinfunction "DDR1_A14_P2") (pintype "output"))
    )
    (net (code "81") (name "unconnected-(U8L-DDR1_A15-PadR1)") (class "Default")
      (node (ref "U8") (pin "R1") (pinfunction "DDR1_A15_R1") (pintype "output"))
    )
    (net (code "82") (name "unconnected-(U8L-DDR1_ATO-PadM7)") (class "Default")
      (node (ref "U8") (pin "M7") (pinfunction "DDR1_ATO_M7") (pintype "passive"))
    )
    (net (code "83") (name "unconnected-(U8L-DDR1_BA0-PadL4)") (class "Default")
      (node (ref "U8") (pin "L4") (pinfunction "DDR1_BA0_L4") (pintype "output"))
    )
    (net (code "84") (name "unconnected-(U8L-DDR1_BA1-PadJ1)") (class "Default")
      (node (ref "U8") (pin "J1") (pinfunction "DDR1_BA1_J1") (pintype "output"))
    )
    (net (code "85") (name "unconnected-(U8L-DDR1_BA2-PadL5)") (class "Default")
      (node (ref "U8") (pin "L5") (pinfunction "DDR1_BA2_L5") (pintype "output"))
    )
    (net (code "86") (name "unconnected-(U8L-DDR1_CASn-PadH1)") (class "Default")
      (node (ref "U8") (pin "H1") (pinfunction "DDR1_CASn_H1") (pintype "output"))
    )
    (net (code "87") (name "unconnected-(U8L-DDR1_ODT0-PadP5)") (class "Default")
      (node (ref "U8") (pin "P5") (pinfunction "DDR1_ODT0_P5") (pintype "output"))
    )
    (net (code "88") (name "unconnected-(U8L-DDR1_ODT1-PadR2)") (class "Default")
      (node (ref "U8") (pin "R2") (pinfunction "DDR1_ODT1_R2") (pintype "output"))
    )
    (net (code "89") (name "unconnected-(U8L-DDR1_RASn-PadL6)") (class "Default")
      (node (ref "U8") (pin "L6") (pinfunction "DDR1_RASn_L6") (pintype "output"))
    )
    (net (code "90") (name "unconnected-(U8L-DDR1_RESET-PadF2)") (class "Default")
      (node (ref "U8") (pin "F2") (pinfunction "DDR1_RESET_F2") (pintype "output"))
    )
    (net (code "91") (name "unconnected-(U8L-DDR1_WEn-PadJ2)") (class "Default")
      (node (ref "U8") (pin "J2") (pinfunction "DDR1_WEn_J2") (pintype "output"))
    )
    (net (code "92") (name "unconnected-(U8L-NC4-PadP7)") (class "Default")
      (node (ref "U8") (pin "P7") (pinfunction "NC4_P7") (pintype "passive"))
    )
    (net (code "93") (name "unconnected-(U8L-NC5-PadR7)") (class "Default")
      (node (ref "U8") (pin "R7") (pinfunction "NC5_R7") (pintype "passive"))
    )
    (net (code "94") (name "unconnected-(U8L-NC6-PadL7)") (class "Default")
      (node (ref "U8") (pin "L7") (pinfunction "NC6_L7") (pintype "passive"))
    )
    (net (code "95") (name "unconnected-(U9-DDR_A0-b-PadAF25)") (class "Default")
      (node (ref "U9") (pin "AF25") (pinfunction "DDR_A0-b_AF25") (pintype "passive"))
    )
    (net (code "96") (name "unconnected-(U9-DDR_A1-b-PadAG24)") (class "Default")
      (node (ref "U9") (pin "AG24") (pinfunction "DDR_A1-b_AG24") (pintype "passive"))
    )
    (net (code "97") (name "unconnected-(U9-DDR_A2-b-PadAF24)") (class "Default")
      (node (ref "U9") (pin "AF24") (pinfunction "DDR_A2-b_AF24") (pintype "passive"))
    )
    (net (code "98") (name "unconnected-(U9-DDR_A3-b-PadAG23)") (class "Default")
      (node (ref "U9") (pin "AG23") (pinfunction "DDR_A3-b_AG23") (pintype "passive"))
    )
    (net (code "99") (name "unconnected-(U9-DDR_A4-b-PadAF22)") (class "Default")
      (node (ref "U9") (pin "AF22") (pinfunction "DDR_A4-b_AF22") (pintype "passive"))
    )
    (net (code "100") (name "unconnected-(U9-DDR_A5-b-PadAG16)") (class "Default")
      (node (ref "U9") (pin "AG16") (pinfunction "DDR_A5-b_AG16") (pintype "passive"))
    )
    (net (code "101") (name "unconnected-(U9-DDR_A6-b-PadAG15)") (class "Default")
      (node (ref "U9") (pin "AG15") (pinfunction "DDR_A6-b_AG15") (pintype "passive"))
    )
    (net (code "102") (name "unconnected-(U9-DDR_A7-b-PadAF15)") (class "Default")
      (node (ref "U9") (pin "AF15") (pinfunction "DDR_A7-b_AF15") (pintype "passive"))
    )
    (net (code "103") (name "unconnected-(U9-DDR_A8-b-PadAG14)") (class "Default")
      (node (ref "U9") (pin "AG14") (pinfunction "DDR_A8-b_AG14") (pintype "passive"))
    )
    (net (code "104") (name "unconnected-(U9-DDR_A9-b-PadAF14)") (class "Default")
      (node (ref "U9") (pin "AF14") (pinfunction "DDR_A9-b_AF14") (pintype "passive"))
    )
    (net (code "105") (name "unconnected-(U9-DDR_CKE0-b-PadAG20)") (class "Default")
      (node (ref "U9") (pin "AG20") (pinfunction "DDR_CKE0-b_AG20") (pintype "passive"))
    )
    (net (code "106") (name "unconnected-(U9-DDR_CKE1-b-PadAF20)") (class "Default")
      (node (ref "U9") (pin "AF20") (pinfunction "DDR_CKE1-b_AF20") (pintype "passive"))
    )
    (net (code "107") (name "unconnected-(U9-DDR_CLK-b-PadAF19)") (class "Default")
      (node (ref "U9") (pin "AF19") (pinfunction "DDR_CLK-b_AF19") (pintype "passive"))
    )
    (net (code "108") (name "unconnected-(U9-DDR_CLKn-b-PadAG19)") (class "Default")
      (node (ref "U9") (pin "AG19") (pinfunction "DDR_CLKn-b_AG19") (pintype "passive"))
    )
    (net (code "109") (name "unconnected-(U9-DDR_CS0-b-PadAF21)") (class "Default")
      (node (ref "U9") (pin "AF21") (pinfunction "DDR_CS0-b_AF21") (pintype "passive"))
    )
    (net (code "110") (name "unconnected-(U9-DDR_CS1-b-PadAG21)") (class "Default")
      (node (ref "U9") (pin "AG21") (pinfunction "DDR_CS1-b_AG21") (pintype "passive"))
    )
    (net (code "111") (name "unconnected-(U9-DDR_D0-b-PadF27)") (class "Default")
      (node (ref "U9") (pin "F27") (pinfunction "DDR_D0-b_F27") (pintype "passive"))
    )
    (net (code "112") (name "unconnected-(U9-DDR_D1-b-PadE26)") (class "Default")
      (node (ref "U9") (pin "E26") (pinfunction "DDR_D1-b_E26") (pintype "passive"))
    )
    (net (code "113") (name "unconnected-(U9-DDR_D2-b-PadE25)") (class "Default")
      (node (ref "U9") (pin "E25") (pinfunction "DDR_D2-b_E25") (pintype "passive"))
    )
    (net (code "114") (name "unconnected-(U9-DDR_D3-b-PadD27)") (class "Default")
      (node (ref "U9") (pin "D27") (pinfunction "DDR_D3-b_D27") (pintype "passive"))
    )
    (net (code "115") (name "unconnected-(U9-DDR_D4-b-PadC27)") (class "Default")
      (node (ref "U9") (pin "C27") (pinfunction "DDR_D4-b_C27") (pintype "passive"))
    )
    (net (code "116") (name "unconnected-(U9-DDR_D5-b-PadC26)") (class "Default")
      (node (ref "U9") (pin "C26") (pinfunction "DDR_D5-b_C26") (pintype "passive"))
    )
    (net (code "117") (name "unconnected-(U9-DDR_D6-b-PadB25)") (class "Default")
      (node (ref "U9") (pin "B25") (pinfunction "DDR_D6-b_B25") (pintype "passive"))
    )
    (net (code "118") (name "unconnected-(U9-DDR_D7-b-PadA24)") (class "Default")
      (node (ref "U9") (pin "A24") (pinfunction "DDR_D7-b_A24") (pintype "passive"))
    )
    (net (code "119") (name "unconnected-(U9-DDR_D8-b-PadB17)") (class "Default")
      (node (ref "U9") (pin "B17") (pinfunction "DDR_D8-b_B17") (pintype "passive"))
    )
    (net (code "120") (name "unconnected-(U9-DDR_D9-b-PadA17)") (class "Default")
      (node (ref "U9") (pin "A17") (pinfunction "DDR_D9-b_A17") (pintype "passive"))
    )
    (net (code "121") (name "unconnected-(U9-DDR_D10-b-PadB16)") (class "Default")
      (node (ref "U9") (pin "B16") (pinfunction "DDR_D10-b_B16") (pintype "passive"))
    )
    (net (code "122") (name "unconnected-(U9-DDR_D11-b-PadA15)") (class "Default")
      (node (ref "U9") (pin "A15") (pinfunction "DDR_D11-b_A15") (pintype "passive"))
    )
    (net (code "123") (name "unconnected-(U9-DDR_D12-b-PadB14)") (class "Default")
      (node (ref "U9") (pin "B14") (pinfunction "DDR_D12-b_B14") (pintype "passive"))
    )
    (net (code "124") (name "unconnected-(U9-DDR_D13-b-PadA14)") (class "Default")
      (node (ref "U9") (pin "A14") (pinfunction "DDR_D13-b_A14") (pintype "passive"))
    )
    (net (code "125") (name "unconnected-(U9-DDR_D14-b-PadB13)") (class "Default")
      (node (ref "U9") (pin "B13") (pinfunction "DDR_D14-b_B13") (pintype "passive"))
    )
    (net (code "126") (name "unconnected-(U9-DDR_D15-b-PadA12)") (class "Default")
      (node (ref "U9") (pin "A12") (pinfunction "DDR_D15-b_A12") (pintype "passive"))
    )
    (net (code "127") (name "unconnected-(U9-DDR_D16-b-PadN25)") (class "Default")
      (node (ref "U9") (pin "N25") (pinfunction "DDR_D16-b_N25") (pintype "passive"))
    )
    (net (code "128") (name "unconnected-(U9-DDR_D17-b-PadM27)") (class "Default")
      (node (ref "U9") (pin "M27") (pinfunction "DDR_D17-b_M27") (pintype "passive"))
    )
    (net (code "129") (name "unconnected-(U9-DDR_D18-b-PadL26)") (class "Default")
      (node (ref "U9") (pin "L26") (pinfunction "DDR_D18-b_L26") (pintype "passive"))
    )
    (net (code "130") (name "unconnected-(U9-DDR_D19-b-PadL25)") (class "Default")
      (node (ref "U9") (pin "L25") (pinfunction "DDR_D19-b_L25") (pintype "passive"))
    )
    (net (code "131") (name "unconnected-(U9-DDR_D20-b-PadK27)") (class "Default")
      (node (ref "U9") (pin "K27") (pinfunction "DDR_D20-b_K27") (pintype "passive"))
    )
    (net (code "132") (name "unconnected-(U9-DDR_D21-b-PadJ25)") (class "Default")
      (node (ref "U9") (pin "J25") (pinfunction "DDR_D21-b_J25") (pintype "passive"))
    )
    (net (code "133") (name "unconnected-(U9-DDR_D22-b-PadJ26)") (class "Default")
      (node (ref "U9") (pin "J26") (pinfunction "DDR_D22-b_J26") (pintype "passive"))
    )
    (net (code "134") (name "unconnected-(U9-DDR_D23-b-PadH27)") (class "Default")
      (node (ref "U9") (pin "H27") (pinfunction "DDR_D23-b_H27") (pintype "passive"))
    )
    (net (code "135") (name "unconnected-(U9-DDR_D24-b-PadA9)") (class "Default")
      (node (ref "U9") (pin "A9") (pinfunction "DDR_D24-b_A9") (pintype "passive"))
    )
    (net (code "136") (name "unconnected-(U9-DDR_D25-b-PadA8)") (class "Default")
      (node (ref "U9") (pin "A8") (pinfunction "DDR_D25-b_A8") (pintype "passive"))
    )
    (net (code "137") (name "unconnected-(U9-DDR_D26-b-PadB8)") (class "Default")
      (node (ref "U9") (pin "B8") (pinfunction "DDR_D26-b_B8") (pintype "passive"))
    )
    (net (code "138") (name "unconnected-(U9-DDR_D27-b-PadB7)") (class "Default")
      (node (ref "U9") (pin "B7") (pinfunction "DDR_D27-b_B7") (pintype "passive"))
    )
    (net (code "139") (name "unconnected-(U9-DDR_D28-b-PadA6)") (class "Default")
      (node (ref "U9") (pin "A6") (pinfunction "DDR_D28-b_A6") (pintype "passive"))
    )
    (net (code "140") (name "unconnected-(U9-DDR_D29-b-PadA5)") (class "Default")
      (node (ref "U9") (pin "A5") (pinfunction "DDR_D29-b_A5") (pintype "passive"))
    )
    (net (code "141") (name "unconnected-(U9-DDR_D30-b-PadB5)") (class "Default")
      (node (ref "U9") (pin "B5") (pinfunction "DDR_D30-b_B5") (pintype "passive"))
    )
    (net (code "142") (name "unconnected-(U9-DDR_D31-b-PadB4)") (class "Default")
      (node (ref "U9") (pin "B4") (pinfunction "DDR_D31-b_B4") (pintype "passive"))
    )
    (net (code "143") (name "unconnected-(U9-DDR_DM0-b-PadB22)") (class "Default")
      (node (ref "U9") (pin "B22") (pinfunction "DDR_DM0-b_B22") (pintype "passive"))
    )
    (net (code "144") (name "unconnected-(U9-DDR_DM1-b-PadA19)") (class "Default")
      (node (ref "U9") (pin "A19") (pinfunction "DDR_DM1-b_A19") (pintype "passive"))
    )
    (net (code "145") (name "unconnected-(U9-DDR_DM2-b-PadG25)") (class "Default")
      (node (ref "U9") (pin "G25") (pinfunction "DDR_DM2-b_G25") (pintype "passive"))
    )
    (net (code "146") (name "unconnected-(U9-DDR_DM3-b-PadA11)") (class "Default")
      (node (ref "U9") (pin "A11") (pinfunction "DDR_DM3-b_A11") (pintype "passive"))
    )
    (net (code "147") (name "unconnected-(U9-DDR_DQS0-b-PadB23)") (class "Default")
      (node (ref "U9") (pin "B23") (pinfunction "DDR_DQS0-b_B23") (pintype "passive"))
    )
    (net (code "148") (name "unconnected-(U9-DDR_DQS0n-b-PadA23)") (class "Default")
      (node (ref "U9") (pin "A23") (pinfunction "DDR_DQS0n-b_A23") (pintype "passive"))
    )
    (net (code "149") (name "unconnected-(U9-DDR_DQS1-b-PadB18)") (class "Default")
      (node (ref "U9") (pin "B18") (pinfunction "DDR_DQS1-b_B18") (pintype "passive"))
    )
    (net (code "150") (name "unconnected-(U9-DDR_DQS1n-b-PadA18)") (class "Default")
      (node (ref "U9") (pin "A18") (pinfunction "DDR_DQS1n-b_A18") (pintype "passive"))
    )
    (net (code "151") (name "unconnected-(U9-DDR_DQS2-b-PadG26)") (class "Default")
      (node (ref "U9") (pin "G26") (pinfunction "DDR_DQS2-b_G26") (pintype "passive"))
    )
    (net (code "152") (name "unconnected-(U9-DDR_DQS2n-b-PadH26)") (class "Default")
      (node (ref "U9") (pin "H26") (pinfunction "DDR_DQS2n-b_H26") (pintype "passive"))
    )
    (net (code "153") (name "unconnected-(U9-DDR_DQS3-b-PadB10)") (class "Default")
      (node (ref "U9") (pin "B10") (pinfunction "DDR_DQS3-b_B10") (pintype "passive"))
    )
    (net (code "154") (name "unconnected-(U9-DDR_DQS3n-b-PadA10)") (class "Default")
      (node (ref "U9") (pin "A10") (pinfunction "DDR_DQS3n-b_A10") (pintype "passive"))
    )
    (net (code "155") (name "unconnected-(U9-DDR_ZQ-b-PadAG12)") (class "Default")
      (node (ref "U9") (pin "AG12") (pinfunction "DDR_ZQ-b_AG12") (pintype "passive"))
    )
    (net (code "156") (name "unconnected-(U9-NC1-PadA27)") (class "Default")
      (node (ref "U9") (pin "A27") (pinfunction "NC1_A27") (pintype "passive"))
    )
    (net (code "157") (name "unconnected-(U9-NC2-PadA1)") (class "Default")
      (node (ref "U9") (pin "A1") (pinfunction "NC2_A1") (pintype "passive"))
    )
    (net (code "158") (name "unconnected-(U9-NC3-PadAG27)") (class "Default")
      (node (ref "U9") (pin "AG27") (pinfunction "NC3_AG27") (pintype "passive"))
    )
    (net (code "159") (name "unconnected-(U9-NC4-PadAG1)") (class "Default")
      (node (ref "U9") (pin "AG1") (pinfunction "NC4_AG1") (pintype "passive"))
    )
  )
)
